# FPGAPower.net
KiCad netlist of a schematic drawn in Altium Designer
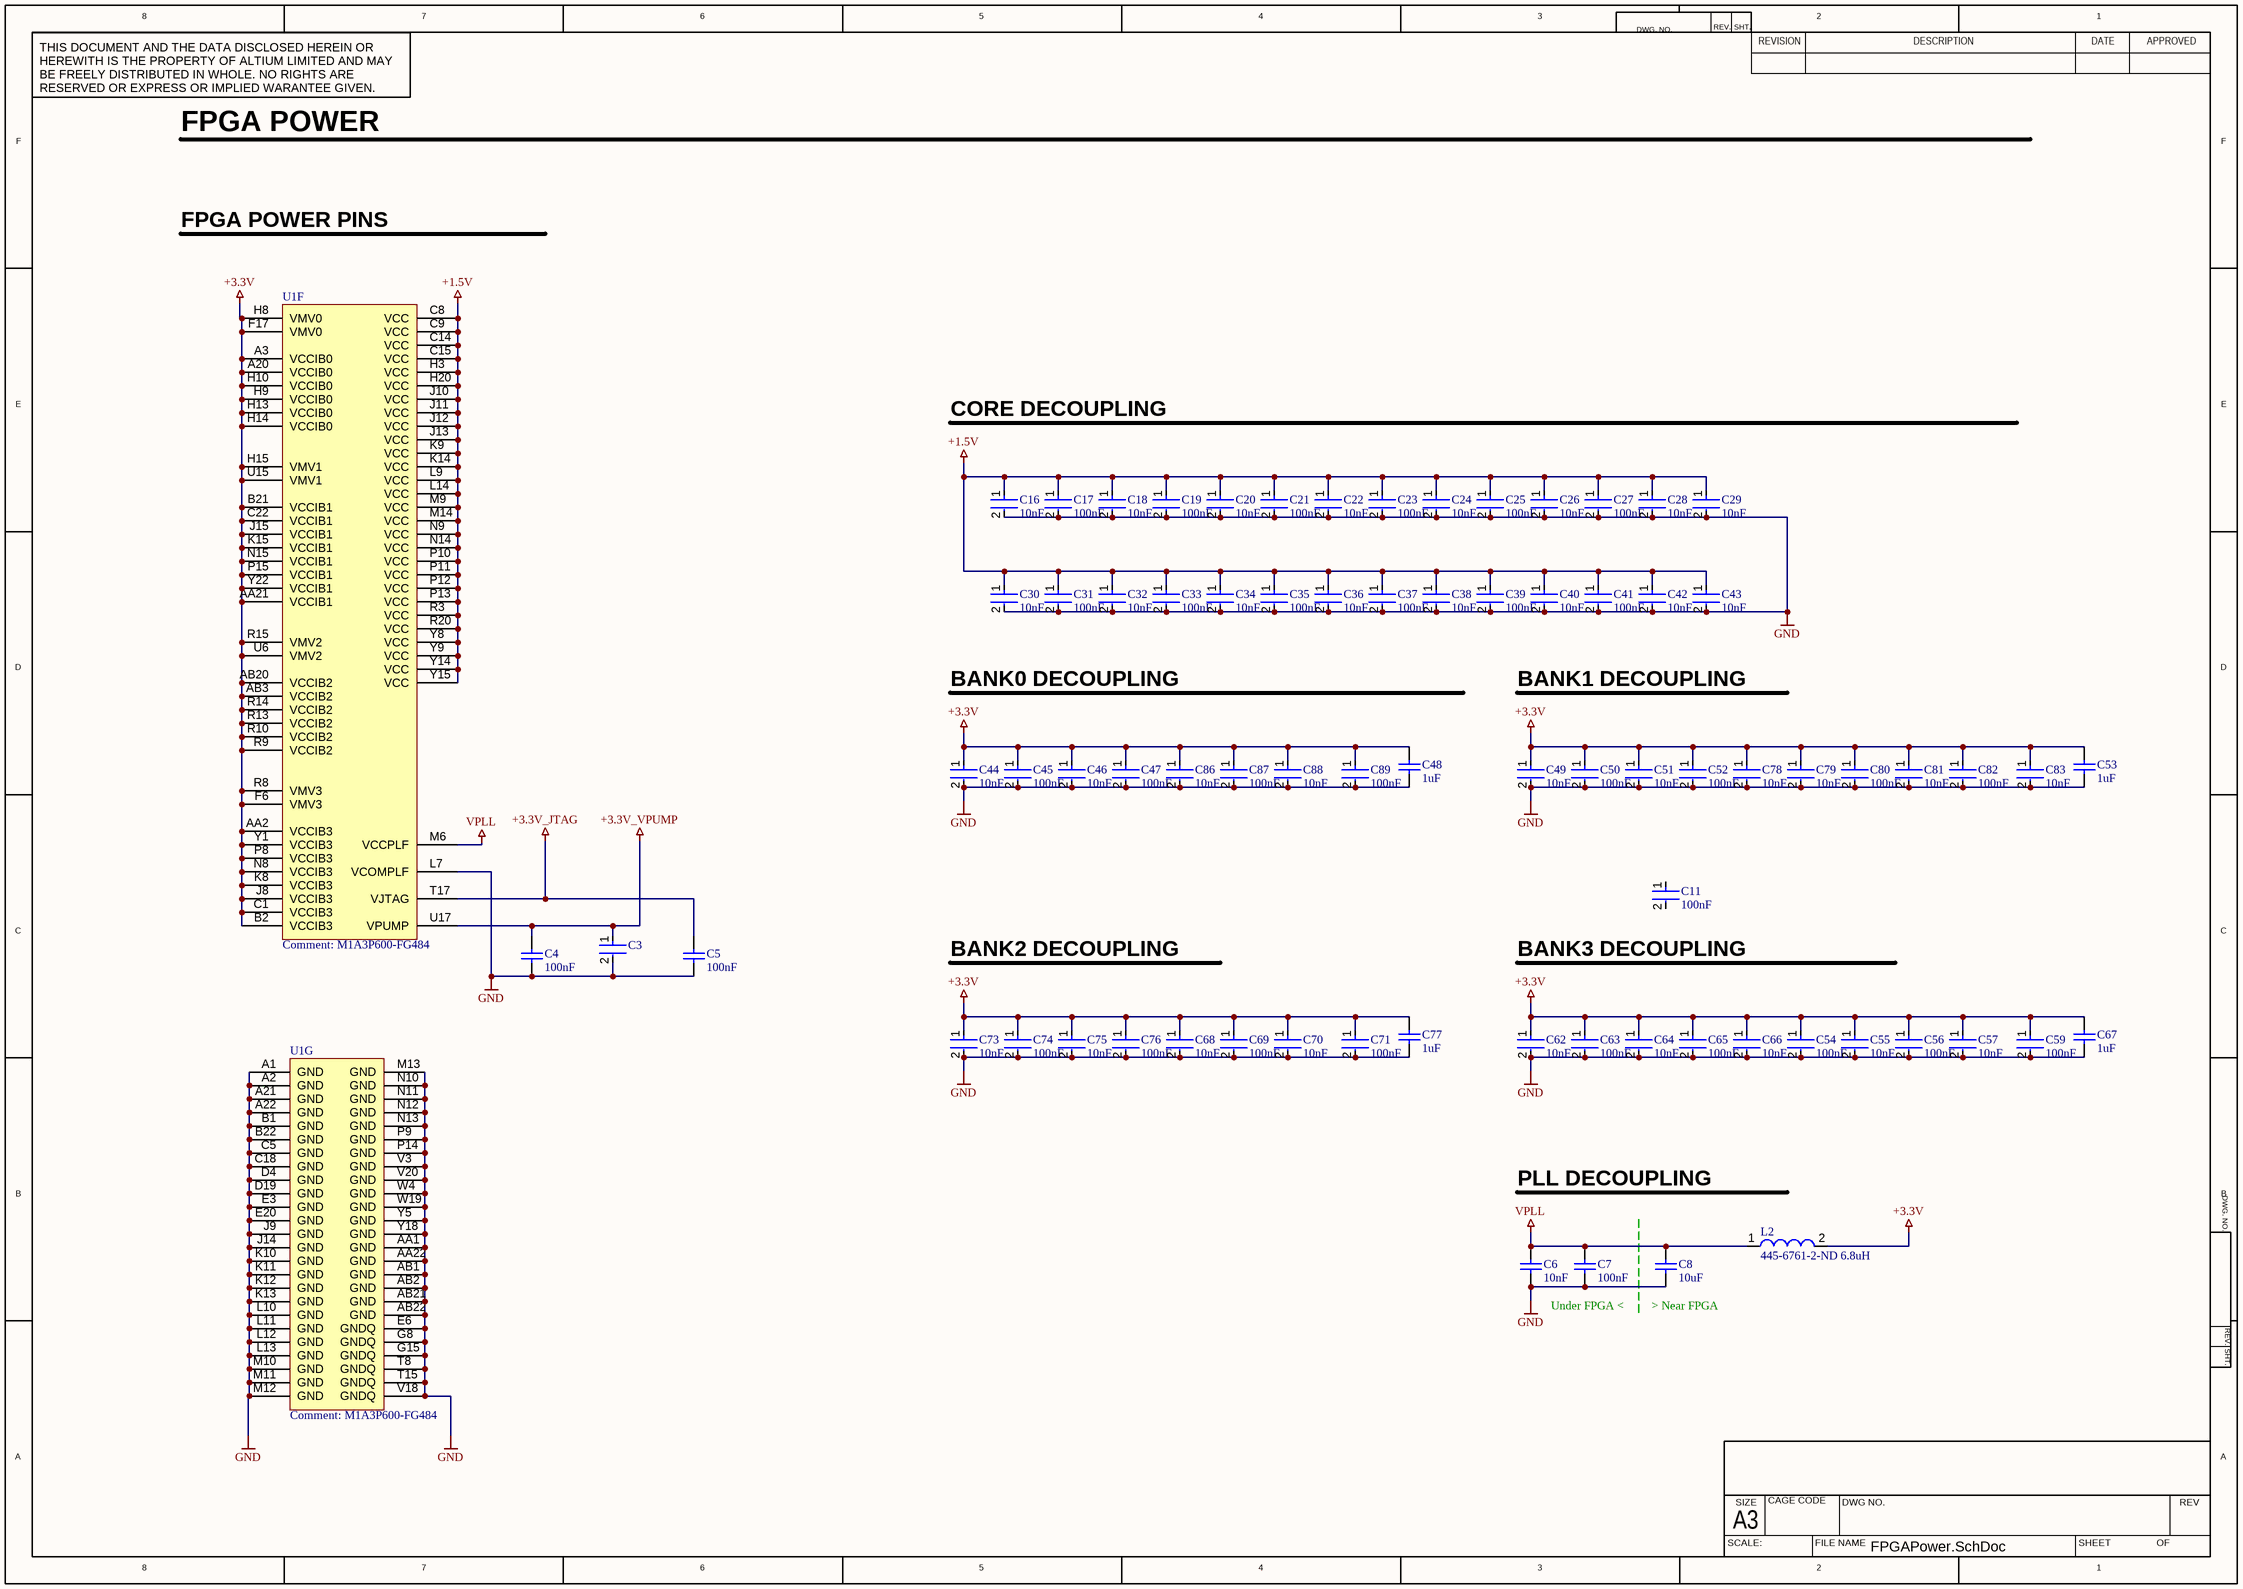
[diagram p0: FPGAPower.SchDoc]

(export (version "E")
  (design (tool "Eeschema 10.0.6"))
  (components
    (comp (ref "C3")
      (value "CC0402KRX5R6BB334")
      (footprint "FP-CC0402-MFG")
      (description "CAP CER 0.33UF 10V X5R 0402")
      (fields
        (field (name "MANUFACTURER") "YAGEO")
        (field (name "OCTOPART") "https://octopart.com/cc0402krx5r6bb334-yageo-21548561")
      )
      (libsource (lib "Altium Content Vault") (part "11868f565c42a9108669ba33697ecf6"))
    )
    (comp (ref "C4")
      (value "100nF")
      (footprint "CAPC1005X60X30ML05T10")
      (fields (field (name "MANUFACTURER") "Kemet") (field (name "PART NUMBER") "C0402C104K8PACTU"))
      (libsource (lib "Altium Content Vault") (part "CAP"))
    )
    (comp (ref "C5")
      (value "100nF")
      (footprint "CAPC1005X60X30ML05T10")
      (fields (field (name "MANUFACTURER") "Kemet") (field (name "PART NUMBER") "C0402C104K8PACTU"))
      (libsource (lib "Altium Content Vault") (part "CAP"))
    )
    (comp (ref "C6")
      (value "10nF")
      (footprint "CAPC0402(1005)60_M")
      (description "CAP 10nF 16V -20% to +80% 0402 (1005 Metric) Thickness 0.6mm SMD")
      (fields (field (name "TOLERANCE") "-20% to +80%"))
      (libsource (lib "Altium Content Vault") (part "CAP"))
    )
    (comp (ref "C7")
      (value "100nF")
      (footprint "CAPC1005X60X30ML05T10")
      (fields (field (name "MANUFACTURER") "Kemet") (field (name "PART NUMBER") "C0402C104K8PACTU"))
      (libsource (lib "Altium Content Vault") (part "CAP"))
    )
    (comp (ref "C8")
      (value "10uF")
      (footprint "CAPC2013X145X20ML20")
      (fields
        (field (name "MANUFACTURER") "TDK")
        (field (name "TOLERANCE") "±10%")
        (field (name "PCN PART NUMBER") "MLCCPartNumberChange30/Nov/2012")
      )
      (libsource (lib "Altium Content Vault") (part "CAP-NP-2"))
    )
    (comp (ref "C11")
      (value "100nF")
      (footprint "FP-GRM155-0_05-IPC_C")
      (fields (field (name "TOLERANCE") "10%") (field (name "VOLTAGE") "25V"))
      (libsource (lib "Altium Content Vault") (part "02cd4be3c70576c341d710602a673aa"))
    )
    (comp (ref "C16")
      (value "10nF")
      (footprint "FP-GRM155-0_05-IPC_C")
      (fields (field (name "TOLERANCE") "10%") (field (name "VOLTAGE") "25V"))
      (libsource (lib "Altium Content Vault") (part "02cd4be3c70576c341d710602a673aa"))
    )
    (comp (ref "C17")
      (value "100nF")
      (footprint "FP-GRM155-0_05-IPC_C")
      (fields (field (name "TOLERANCE") "10%") (field (name "VOLTAGE") "25V"))
      (libsource (lib "Altium Content Vault") (part "02cd4be3c70576c341d710602a673aa"))
    )
    (comp (ref "C18")
      (value "10nF")
      (footprint "FP-GRM155-0_05-IPC_C")
      (fields (field (name "TOLERANCE") "10%") (field (name "VOLTAGE") "25V"))
      (libsource (lib "Altium Content Vault") (part "02cd4be3c70576c341d710602a673aa"))
    )
    (comp (ref "C19")
      (value "100nF")
      (footprint "FP-GRM155-0_05-IPC_C")
      (fields (field (name "TOLERANCE") "10%") (field (name "VOLTAGE") "25V"))
      (libsource (lib "Altium Content Vault") (part "02cd4be3c70576c341d710602a673aa"))
    )
    (comp (ref "C20")
      (value "10nF")
      (footprint "FP-GRM155-0_05-IPC_C")
      (fields (field (name "TOLERANCE") "10%") (field (name "VOLTAGE") "25V"))
      (libsource (lib "Altium Content Vault") (part "02cd4be3c70576c341d710602a673aa"))
    )
    (comp (ref "C21")
      (value "100nF")
      (footprint "FP-GRM155-0_05-IPC_C")
      (fields (field (name "TOLERANCE") "10%") (field (name "VOLTAGE") "25V"))
      (libsource (lib "Altium Content Vault") (part "02cd4be3c70576c341d710602a673aa"))
    )
    (comp (ref "C22")
      (value "10nF")
      (footprint "FP-GRM155-0_05-IPC_C")
      (fields (field (name "TOLERANCE") "10%") (field (name "VOLTAGE") "25V"))
      (libsource (lib "Altium Content Vault") (part "02cd4be3c70576c341d710602a673aa"))
    )
    (comp (ref "C23")
      (value "100nF")
      (footprint "FP-GRM155-0_05-IPC_C")
      (fields (field (name "TOLERANCE") "10%") (field (name "VOLTAGE") "25V"))
      (libsource (lib "Altium Content Vault") (part "02cd4be3c70576c341d710602a673aa"))
    )
    (comp (ref "C24")
      (value "10nF")
      (footprint "FP-GRM155-0_05-IPC_C")
      (fields (field (name "TOLERANCE") "10%") (field (name "VOLTAGE") "25V"))
      (libsource (lib "Altium Content Vault") (part "02cd4be3c70576c341d710602a673aa"))
    )
    (comp (ref "C25")
      (value "100nF")
      (footprint "FP-GRM155-0_05-IPC_C")
      (fields (field (name "TOLERANCE") "10%") (field (name "VOLTAGE") "25V"))
      (libsource (lib "Altium Content Vault") (part "02cd4be3c70576c341d710602a673aa"))
    )
    (comp (ref "C26")
      (value "10nF")
      (footprint "FP-GRM155-0_05-IPC_C")
      (fields (field (name "TOLERANCE") "10%") (field (name "VOLTAGE") "25V"))
      (libsource (lib "Altium Content Vault") (part "02cd4be3c70576c341d710602a673aa"))
    )
    (comp (ref "C27")
      (value "100nF")
      (footprint "FP-GRM155-0_05-IPC_C")
      (fields (field (name "TOLERANCE") "10%") (field (name "VOLTAGE") "25V"))
      (libsource (lib "Altium Content Vault") (part "02cd4be3c70576c341d710602a673aa"))
    )
    (comp (ref "C28")
      (value "10nF")
      (footprint "FP-GRM155-0_05-IPC_C")
      (fields (field (name "TOLERANCE") "10%") (field (name "VOLTAGE") "25V"))
      (libsource (lib "Altium Content Vault") (part "02cd4be3c70576c341d710602a673aa"))
    )
    (comp (ref "C29")
      (value "10nF")
      (footprint "FP-GRM155-0_05-IPC_C")
      (fields (field (name "TOLERANCE") "10%") (field (name "VOLTAGE") "25V"))
      (libsource (lib "Altium Content Vault") (part "02cd4be3c70576c341d710602a673aa"))
    )
    (comp (ref "C30")
      (value "10nF")
      (footprint "FP-GRM155-0_05-IPC_C")
      (fields (field (name "TOLERANCE") "10%") (field (name "VOLTAGE") "25V"))
      (libsource (lib "Altium Content Vault") (part "02cd4be3c70576c341d710602a673aa"))
    )
    (comp (ref "C31")
      (value "100nF")
      (footprint "FP-GRM155-0_05-IPC_C")
      (fields (field (name "TOLERANCE") "10%") (field (name "VOLTAGE") "25V"))
      (libsource (lib "Altium Content Vault") (part "02cd4be3c70576c341d710602a673aa"))
    )
    (comp (ref "C32")
      (value "10nF")
      (footprint "FP-GRM155-0_05-IPC_C")
      (fields (field (name "TOLERANCE") "10%") (field (name "VOLTAGE") "25V"))
      (libsource (lib "Altium Content Vault") (part "02cd4be3c70576c341d710602a673aa"))
    )
    (comp (ref "C33")
      (value "100nF")
      (footprint "FP-GRM155-0_05-IPC_C")
      (fields (field (name "TOLERANCE") "10%") (field (name "VOLTAGE") "25V"))
      (libsource (lib "Altium Content Vault") (part "02cd4be3c70576c341d710602a673aa"))
    )
    (comp (ref "C34")
      (value "10nF")
      (footprint "FP-GRM155-0_05-IPC_C")
      (fields (field (name "TOLERANCE") "10%") (field (name "VOLTAGE") "25V"))
      (libsource (lib "Altium Content Vault") (part "02cd4be3c70576c341d710602a673aa"))
    )
    (comp (ref "C35")
      (value "100nF")
      (footprint "FP-GRM155-0_05-IPC_C")
      (fields (field (name "TOLERANCE") "10%") (field (name "VOLTAGE") "25V"))
      (libsource (lib "Altium Content Vault") (part "02cd4be3c70576c341d710602a673aa"))
    )
    (comp (ref "C36")
      (value "10nF")
      (footprint "FP-GRM155-0_05-IPC_C")
      (fields (field (name "TOLERANCE") "10%") (field (name "VOLTAGE") "25V"))
      (libsource (lib "Altium Content Vault") (part "02cd4be3c70576c341d710602a673aa"))
    )
    (comp (ref "C37")
      (value "100nF")
      (footprint "FP-GRM155-0_05-IPC_C")
      (fields (field (name "TOLERANCE") "10%") (field (name "VOLTAGE") "25V"))
      (libsource (lib "Altium Content Vault") (part "02cd4be3c70576c341d710602a673aa"))
    )
    (comp (ref "C38")
      (value "10nF")
      (footprint "FP-GRM155-0_05-IPC_C")
      (fields (field (name "TOLERANCE") "10%") (field (name "VOLTAGE") "25V"))
      (libsource (lib "Altium Content Vault") (part "02cd4be3c70576c341d710602a673aa"))
    )
    (comp (ref "C39")
      (value "100nF")
      (footprint "FP-GRM155-0_05-IPC_C")
      (fields (field (name "TOLERANCE") "10%") (field (name "VOLTAGE") "25V"))
      (libsource (lib "Altium Content Vault") (part "02cd4be3c70576c341d710602a673aa"))
    )
    (comp (ref "C40")
      (value "10nF")
      (footprint "FP-GRM155-0_05-IPC_C")
      (fields (field (name "TOLERANCE") "10%") (field (name "VOLTAGE") "25V"))
      (libsource (lib "Altium Content Vault") (part "02cd4be3c70576c341d710602a673aa"))
    )
    (comp (ref "C41")
      (value "100nF")
      (footprint "FP-GRM155-0_05-IPC_C")
      (fields (field (name "TOLERANCE") "10%") (field (name "VOLTAGE") "25V"))
      (libsource (lib "Altium Content Vault") (part "02cd4be3c70576c341d710602a673aa"))
    )
    (comp (ref "C42")
      (value "10nF")
      (footprint "FP-GRM155-0_05-IPC_C")
      (fields (field (name "TOLERANCE") "10%") (field (name "VOLTAGE") "25V"))
      (libsource (lib "Altium Content Vault") (part "02cd4be3c70576c341d710602a673aa"))
    )
    (comp (ref "C43")
      (value "10nF")
      (footprint "FP-GRM155-0_05-IPC_C")
      (fields (field (name "TOLERANCE") "10%") (field (name "VOLTAGE") "25V"))
      (libsource (lib "Altium Content Vault") (part "02cd4be3c70576c341d710602a673aa"))
    )
    (comp (ref "C44")
      (value "10nF")
      (footprint "FP-GRM155-0_05-IPC_C")
      (fields (field (name "TOLERANCE") "10%") (field (name "VOLTAGE") "25V"))
      (libsource (lib "Altium Content Vault") (part "02cd4be3c70576c341d710602a673aa"))
    )
    (comp (ref "C45")
      (value "100nF")
      (footprint "FP-GRM155-0_05-IPC_C")
      (fields (field (name "TOLERANCE") "10%") (field (name "VOLTAGE") "25V"))
      (libsource (lib "Altium Content Vault") (part "02cd4be3c70576c341d710602a673aa"))
    )
    (comp (ref "C46")
      (value "10nF")
      (footprint "FP-GRM155-0_05-IPC_C")
      (fields (field (name "TOLERANCE") "10%") (field (name "VOLTAGE") "25V"))
      (libsource (lib "Altium Content Vault") (part "02cd4be3c70576c341d710602a673aa"))
    )
    (comp (ref "C47")
      (value "100nF")
      (footprint "FP-GRM155-0_05-IPC_C")
      (fields (field (name "TOLERANCE") "10%") (field (name "VOLTAGE") "25V"))
      (libsource (lib "Altium Content Vault") (part "02cd4be3c70576c341d710602a673aa"))
    )
    (comp (ref "C48")
      (value "1uF")
      (footprint "CAPC1608X90X20LL10")
      (description "Chip Capacitor, 1 uF, +/- 10%, 50 V, -55 to 85 degC, 0603 (1608 Metric), RoHS, Tape and Reel")
      (fields
        (field (name "MANUFACTURER") "TDK")
        (field (name "PCN PART NUMBER") "MLCCPartNumberChange30/Nov/2012")
      )
      (libsource (lib "Altium Content Vault") (part "CAP-NP-2"))
    )
    (comp (ref "C49")
      (value "10nF")
      (footprint "FP-GRM155-0_05-IPC_C")
      (fields (field (name "TOLERANCE") "10%") (field (name "VOLTAGE") "25V"))
      (libsource (lib "Altium Content Vault") (part "02cd4be3c70576c341d710602a673aa"))
    )
    (comp (ref "C50")
      (value "100nF")
      (footprint "FP-GRM155-0_05-IPC_C")
      (fields (field (name "TOLERANCE") "10%") (field (name "VOLTAGE") "25V"))
      (libsource (lib "Altium Content Vault") (part "02cd4be3c70576c341d710602a673aa"))
    )
    (comp (ref "C51")
      (value "10nF")
      (footprint "FP-GRM155-0_05-IPC_C")
      (fields (field (name "TOLERANCE") "10%") (field (name "VOLTAGE") "25V"))
      (libsource (lib "Altium Content Vault") (part "02cd4be3c70576c341d710602a673aa"))
    )
    (comp (ref "C52")
      (value "100nF")
      (footprint "FP-GRM155-0_05-IPC_C")
      (fields (field (name "TOLERANCE") "10%") (field (name "VOLTAGE") "25V"))
      (libsource (lib "Altium Content Vault") (part "02cd4be3c70576c341d710602a673aa"))
    )
    (comp (ref "C53")
      (value "1uF")
      (footprint "CAPC1608X90X20LL10")
      (description "Chip Capacitor, 1 uF, +/- 10%, 50 V, -55 to 85 degC, 0603 (1608 Metric), RoHS, Tape and Reel")
      (fields
        (field (name "MANUFACTURER") "TDK")
        (field (name "PCN PART NUMBER") "MLCCPartNumberChange30/Nov/2012")
      )
      (libsource (lib "Altium Content Vault") (part "CAP-NP-2"))
    )
    (comp (ref "C54")
      (value "100nF")
      (footprint "FP-GRM155-0_05-IPC_C")
      (fields (field (name "TOLERANCE") "10%") (field (name "VOLTAGE") "25V"))
      (libsource (lib "Altium Content Vault") (part "02cd4be3c70576c341d710602a673aa"))
    )
    (comp (ref "C55")
      (value "10nF")
      (footprint "FP-GRM155-0_05-IPC_C")
      (fields (field (name "TOLERANCE") "10%") (field (name "VOLTAGE") "25V"))
      (libsource (lib "Altium Content Vault") (part "02cd4be3c70576c341d710602a673aa"))
    )
    (comp (ref "C56")
      (value "100nF")
      (footprint "FP-GRM155-0_05-IPC_C")
      (fields (field (name "TOLERANCE") "10%") (field (name "VOLTAGE") "25V"))
      (libsource (lib "Altium Content Vault") (part "02cd4be3c70576c341d710602a673aa"))
    )
    (comp (ref "C57")
      (value "10nF")
      (footprint "FP-GRM155-0_05-IPC_C")
      (fields (field (name "TOLERANCE") "10%") (field (name "VOLTAGE") "25V"))
      (libsource (lib "Altium Content Vault") (part "02cd4be3c70576c341d710602a673aa"))
    )
    (comp (ref "C59")
      (value "100nF")
      (footprint "FP-GRM155-0_05-IPC_C")
      (fields (field (name "TOLERANCE") "10%") (field (name "VOLTAGE") "25V"))
      (libsource (lib "Altium Content Vault") (part "02cd4be3c70576c341d710602a673aa"))
    )
    (comp (ref "C62")
      (value "10nF")
      (footprint "FP-GRM155-0_05-IPC_C")
      (fields (field (name "TOLERANCE") "10%") (field (name "VOLTAGE") "25V"))
      (libsource (lib "Altium Content Vault") (part "02cd4be3c70576c341d710602a673aa"))
    )
    (comp (ref "C63")
      (value "100nF")
      (footprint "FP-GRM155-0_05-IPC_C")
      (fields (field (name "TOLERANCE") "10%") (field (name "VOLTAGE") "25V"))
      (libsource (lib "Altium Content Vault") (part "02cd4be3c70576c341d710602a673aa"))
    )
    (comp (ref "C64")
      (value "10nF")
      (footprint "FP-GRM155-0_05-IPC_C")
      (fields (field (name "TOLERANCE") "10%") (field (name "VOLTAGE") "25V"))
      (libsource (lib "Altium Content Vault") (part "02cd4be3c70576c341d710602a673aa"))
    )
    (comp (ref "C65")
      (value "100nF")
      (footprint "FP-GRM155-0_05-IPC_C")
      (fields (field (name "TOLERANCE") "10%") (field (name "VOLTAGE") "25V"))
      (libsource (lib "Altium Content Vault") (part "02cd4be3c70576c341d710602a673aa"))
    )
    (comp (ref "C66")
      (value "10nF")
      (footprint "FP-GRM155-0_05-IPC_C")
      (fields (field (name "TOLERANCE") "10%") (field (name "VOLTAGE") "25V"))
      (libsource (lib "Altium Content Vault") (part "02cd4be3c70576c341d710602a673aa"))
    )
    (comp (ref "C67")
      (value "1uF")
      (footprint "CAPC1608X90X20LL10")
      (description "Chip Capacitor, 1 uF, +/- 10%, 50 V, -55 to 85 degC, 0603 (1608 Metric), RoHS, Tape and Reel")
      (fields
        (field (name "MANUFACTURER") "TDK")
        (field (name "PCN PART NUMBER") "MLCCPartNumberChange30/Nov/2012")
      )
      (libsource (lib "Altium Content Vault") (part "CAP-NP-2"))
    )
    (comp (ref "C68")
      (value "10nF")
      (footprint "FP-GRM155-0_05-IPC_C")
      (fields (field (name "TOLERANCE") "10%") (field (name "VOLTAGE") "25V"))
      (libsource (lib "Altium Content Vault") (part "02cd4be3c70576c341d710602a673aa"))
    )
    (comp (ref "C69")
      (value "100nF")
      (footprint "FP-GRM155-0_05-IPC_C")
      (fields (field (name "TOLERANCE") "10%") (field (name "VOLTAGE") "25V"))
      (libsource (lib "Altium Content Vault") (part "02cd4be3c70576c341d710602a673aa"))
    )
    (comp (ref "C70")
      (value "10nF")
      (footprint "FP-GRM155-0_05-IPC_C")
      (fields (field (name "TOLERANCE") "10%") (field (name "VOLTAGE") "25V"))
      (libsource (lib "Altium Content Vault") (part "02cd4be3c70576c341d710602a673aa"))
    )
    (comp (ref "C71")
      (value "100nF")
      (footprint "FP-GRM155-0_05-IPC_C")
      (fields (field (name "TOLERANCE") "10%") (field (name "VOLTAGE") "25V"))
      (libsource (lib "Altium Content Vault") (part "02cd4be3c70576c341d710602a673aa"))
    )
    (comp (ref "C73")
      (value "10nF")
      (footprint "FP-GRM155-0_05-IPC_C")
      (fields (field (name "TOLERANCE") "10%") (field (name "VOLTAGE") "25V"))
      (libsource (lib "Altium Content Vault") (part "02cd4be3c70576c341d710602a673aa"))
    )
    (comp (ref "C74")
      (value "100nF")
      (footprint "FP-GRM155-0_05-IPC_C")
      (fields (field (name "TOLERANCE") "10%") (field (name "VOLTAGE") "25V"))
      (libsource (lib "Altium Content Vault") (part "02cd4be3c70576c341d710602a673aa"))
    )
    (comp (ref "C75")
      (value "10nF")
      (footprint "FP-GRM155-0_05-IPC_C")
      (fields (field (name "TOLERANCE") "10%") (field (name "VOLTAGE") "25V"))
      (libsource (lib "Altium Content Vault") (part "02cd4be3c70576c341d710602a673aa"))
    )
    (comp (ref "C76")
      (value "100nF")
      (footprint "FP-GRM155-0_05-IPC_C")
      (fields (field (name "TOLERANCE") "10%") (field (name "VOLTAGE") "25V"))
      (libsource (lib "Altium Content Vault") (part "02cd4be3c70576c341d710602a673aa"))
    )
    (comp (ref "C77")
      (value "1uF")
      (footprint "CAPC1608X90X20LL10")
      (description "Chip Capacitor, 1 uF, +/- 10%, 50 V, -55 to 85 degC, 0603 (1608 Metric), RoHS, Tape and Reel")
      (fields
        (field (name "MANUFACTURER") "TDK")
        (field (name "PCN PART NUMBER") "MLCCPartNumberChange30/Nov/2012")
      )
      (libsource (lib "Altium Content Vault") (part "CAP-NP-2"))
    )
    (comp (ref "C78")
      (value "10nF")
      (footprint "FP-GRM155-0_05-IPC_C")
      (fields (field (name "TOLERANCE") "10%") (field (name "VOLTAGE") "25V"))
      (libsource (lib "Altium Content Vault") (part "02cd4be3c70576c341d710602a673aa"))
    )
    (comp (ref "C79")
      (value "10nF")
      (footprint "FP-GRM155-0_05-IPC_C")
      (fields (field (name "TOLERANCE") "10%") (field (name "VOLTAGE") "25V"))
      (libsource (lib "Altium Content Vault") (part "02cd4be3c70576c341d710602a673aa"))
    )
    (comp (ref "C80")
      (value "100nF")
      (footprint "FP-GRM155-0_05-IPC_C")
      (fields (field (name "TOLERANCE") "10%") (field (name "VOLTAGE") "25V"))
      (libsource (lib "Altium Content Vault") (part "02cd4be3c70576c341d710602a673aa"))
    )
    (comp (ref "C81")
      (value "10nF")
      (footprint "FP-GRM155-0_05-IPC_C")
      (fields (field (name "TOLERANCE") "10%") (field (name "VOLTAGE") "25V"))
      (libsource (lib "Altium Content Vault") (part "02cd4be3c70576c341d710602a673aa"))
    )
    (comp (ref "C82")
      (value "100nF")
      (footprint "FP-GRM155-0_05-IPC_C")
      (fields (field (name "TOLERANCE") "10%") (field (name "VOLTAGE") "25V"))
      (libsource (lib "Altium Content Vault") (part "02cd4be3c70576c341d710602a673aa"))
    )
    (comp (ref "C83")
      (value "10nF")
      (footprint "FP-GRM155-0_05-IPC_C")
      (fields (field (name "TOLERANCE") "10%") (field (name "VOLTAGE") "25V"))
      (libsource (lib "Altium Content Vault") (part "02cd4be3c70576c341d710602a673aa"))
    )
    (comp (ref "C86")
      (value "10nF")
      (footprint "FP-GRM155-0_05-IPC_C")
      (fields (field (name "TOLERANCE") "10%") (field (name "VOLTAGE") "25V"))
      (libsource (lib "Altium Content Vault") (part "02cd4be3c70576c341d710602a673aa"))
    )
    (comp (ref "C87")
      (value "100nF")
      (footprint "FP-GRM155-0_05-IPC_C")
      (fields (field (name "TOLERANCE") "10%") (field (name "VOLTAGE") "25V"))
      (libsource (lib "Altium Content Vault") (part "02cd4be3c70576c341d710602a673aa"))
    )
    (comp (ref "C88")
      (value "10nF")
      (footprint "FP-GRM155-0_05-IPC_C")
      (fields (field (name "TOLERANCE") "10%") (field (name "VOLTAGE") "25V"))
      (libsource (lib "Altium Content Vault") (part "02cd4be3c70576c341d710602a673aa"))
    )
    (comp (ref "C89")
      (value "100nF")
      (footprint "FP-GRM155-0_05-IPC_C")
      (fields (field (name "TOLERANCE") "10%") (field (name "VOLTAGE") "25V"))
      (libsource (lib "Altium Content Vault") (part "02cd4be3c70576c341d710602a673aa"))
    )
    (comp (ref "L2")
      (value "445-6761-2-ND 6.8uH")
      (footprint "SMD-0805")
      (description "SMD-Multilayer Inductor WE-MI, L = 1.00 µH")
      (libsource (lib "Altium Content Vault") (part "PAS-IND-INDUCTOR-2"))
    )
    (comp (ref "U1")
      (value "M1A3P600-FG484")
      (footprint "FG484")
      (libsource (lib "Altium Content Vault") (part "FPGA-ACTPA3-A3P600-GA484"))
    )
  )
  (nets
    (net (code "1") (name "+1.5V") (class "Default")
      (node (ref "C16") (pin "1") (pinfunction "1_1") (pintype "passive"))
      (node (ref "C17") (pin "1") (pinfunction "1_1") (pintype "passive"))
      (node (ref "C18") (pin "1") (pinfunction "1_1") (pintype "passive"))
      (node (ref "C19") (pin "1") (pinfunction "1_1") (pintype "passive"))
      (node (ref "C20") (pin "1") (pinfunction "1_1") (pintype "passive"))
      (node (ref "C21") (pin "1") (pinfunction "1_1") (pintype "passive"))
      (node (ref "C22") (pin "1") (pinfunction "1_1") (pintype "passive"))
      (node (ref "C23") (pin "1") (pinfunction "1_1") (pintype "passive"))
      (node (ref "C24") (pin "1") (pinfunction "1_1") (pintype "passive"))
      (node (ref "C25") (pin "1") (pinfunction "1_1") (pintype "passive"))
      (node (ref "C26") (pin "1") (pinfunction "1_1") (pintype "passive"))
      (node (ref "C27") (pin "1") (pinfunction "1_1") (pintype "passive"))
      (node (ref "C28") (pin "1") (pinfunction "1_1") (pintype "passive"))
      (node (ref "C29") (pin "1") (pinfunction "1_1") (pintype "passive"))
      (node (ref "C30") (pin "1") (pinfunction "1_1") (pintype "passive"))
      (node (ref "C31") (pin "1") (pinfunction "1_1") (pintype "passive"))
      (node (ref "C32") (pin "1") (pinfunction "1_1") (pintype "passive"))
      (node (ref "C33") (pin "1") (pinfunction "1_1") (pintype "passive"))
      (node (ref "C34") (pin "1") (pinfunction "1_1") (pintype "passive"))
      (node (ref "C35") (pin "1") (pinfunction "1_1") (pintype "passive"))
      (node (ref "C36") (pin "1") (pinfunction "1_1") (pintype "passive"))
      (node (ref "C37") (pin "1") (pinfunction "1_1") (pintype "passive"))
      (node (ref "C38") (pin "1") (pinfunction "1_1") (pintype "passive"))
      (node (ref "C39") (pin "1") (pinfunction "1_1") (pintype "passive"))
      (node (ref "C40") (pin "1") (pinfunction "1_1") (pintype "passive"))
      (node (ref "C41") (pin "1") (pinfunction "1_1") (pintype "passive"))
      (node (ref "C42") (pin "1") (pinfunction "1_1") (pintype "passive"))
      (node (ref "C43") (pin "1") (pinfunction "1_1") (pintype "passive"))
      (node (ref "U1") (pin "C14") (pinfunction "VCC_C14") (pintype "power_in"))
      (node (ref "U1") (pin "C15") (pinfunction "VCC_C15") (pintype "power_in"))
      (node (ref "U1") (pin "C8") (pinfunction "VCC_C8") (pintype "power_in"))
      (node (ref "U1") (pin "C9") (pinfunction "VCC_C9") (pintype "power_in"))
      (node (ref "U1") (pin "H20") (pinfunction "VCC_H20") (pintype "power_in"))
      (node (ref "U1") (pin "H3") (pinfunction "VCC_H3") (pintype "power_in"))
      (node (ref "U1") (pin "J10") (pinfunction "VCC_J10") (pintype "power_in"))
      (node (ref "U1") (pin "J11") (pinfunction "VCC_J11") (pintype "power_in"))
      (node (ref "U1") (pin "J12") (pinfunction "VCC_J12") (pintype "power_in"))
      (node (ref "U1") (pin "J13") (pinfunction "VCC_J13") (pintype "power_in"))
      (node (ref "U1") (pin "K14") (pinfunction "VCC_K14") (pintype "power_in"))
      (node (ref "U1") (pin "K9") (pinfunction "VCC_K9") (pintype "power_in"))
      (node (ref "U1") (pin "L14") (pinfunction "VCC_L14") (pintype "power_in"))
      (node (ref "U1") (pin "L9") (pinfunction "VCC_L9") (pintype "power_in"))
      (node (ref "U1") (pin "M14") (pinfunction "VCC_M14") (pintype "power_in"))
      (node (ref "U1") (pin "M9") (pinfunction "VCC_M9") (pintype "power_in"))
      (node (ref "U1") (pin "N14") (pinfunction "VCC_N14") (pintype "power_in"))
      (node (ref "U1") (pin "N9") (pinfunction "VCC_N9") (pintype "power_in"))
      (node (ref "U1") (pin "P10") (pinfunction "VCC_P10") (pintype "power_in"))
      (node (ref "U1") (pin "P11") (pinfunction "VCC_P11") (pintype "power_in"))
      (node (ref "U1") (pin "P12") (pinfunction "VCC_P12") (pintype "power_in"))
      (node (ref "U1") (pin "P13") (pinfunction "VCC_P13") (pintype "power_in"))
      (node (ref "U1") (pin "R20") (pinfunction "VCC_R20") (pintype "power_in"))
      (node (ref "U1") (pin "R3") (pinfunction "VCC_R3") (pintype "power_in"))
      (node (ref "U1") (pin "Y14") (pinfunction "VCC_Y14") (pintype "power_in"))
      (node (ref "U1") (pin "Y15") (pinfunction "VCC_Y15") (pintype "power_in"))
      (node (ref "U1") (pin "Y8") (pinfunction "VCC_Y8") (pintype "power_in"))
      (node (ref "U1") (pin "Y9") (pinfunction "VCC_Y9") (pintype "power_in"))
    )
    (net (code "2") (name "+3.3V") (class "Default")
      (node (ref "C44") (pin "1") (pinfunction "1_1") (pintype "passive"))
      (node (ref "C45") (pin "1") (pinfunction "1_1") (pintype "passive"))
      (node (ref "C46") (pin "1") (pinfunction "1_1") (pintype "passive"))
      (node (ref "C47") (pin "1") (pinfunction "1_1") (pintype "passive"))
      (node (ref "C48") (pin "2") (pinfunction "2_2") (pintype "passive"))
      (node (ref "C49") (pin "1") (pinfunction "1_1") (pintype "passive"))
      (node (ref "C50") (pin "1") (pinfunction "1_1") (pintype "passive"))
      (node (ref "C51") (pin "1") (pinfunction "1_1") (pintype "passive"))
      (node (ref "C52") (pin "1") (pinfunction "1_1") (pintype "passive"))
      (node (ref "C53") (pin "2") (pinfunction "2_2") (pintype "passive"))
      (node (ref "C54") (pin "1") (pinfunction "1_1") (pintype "passive"))
      (node (ref "C55") (pin "1") (pinfunction "1_1") (pintype "passive"))
      (node (ref "C56") (pin "1") (pinfunction "1_1") (pintype "passive"))
      (node (ref "C57") (pin "1") (pinfunction "1_1") (pintype "passive"))
      (node (ref "C59") (pin "1") (pinfunction "1_1") (pintype "passive"))
      (node (ref "C62") (pin "1") (pinfunction "1_1") (pintype "passive"))
      (node (ref "C63") (pin "1") (pinfunction "1_1") (pintype "passive"))
      (node (ref "C64") (pin "1") (pinfunction "1_1") (pintype "passive"))
      (node (ref "C65") (pin "1") (pinfunction "1_1") (pintype "passive"))
      (node (ref "C66") (pin "1") (pinfunction "1_1") (pintype "passive"))
      (node (ref "C67") (pin "2") (pinfunction "2_2") (pintype "passive"))
      (node (ref "C68") (pin "1") (pinfunction "1_1") (pintype "passive"))
      (node (ref "C69") (pin "1") (pinfunction "1_1") (pintype "passive"))
      (node (ref "C70") (pin "1") (pinfunction "1_1") (pintype "passive"))
      (node (ref "C71") (pin "1") (pinfunction "1_1") (pintype "passive"))
      (node (ref "C73") (pin "1") (pinfunction "1_1") (pintype "passive"))
      (node (ref "C74") (pin "1") (pinfunction "1_1") (pintype "passive"))
      (node (ref "C75") (pin "1") (pinfunction "1_1") (pintype "passive"))
      (node (ref "C76") (pin "1") (pinfunction "1_1") (pintype "passive"))
      (node (ref "C77") (pin "2") (pinfunction "2_2") (pintype "passive"))
      (node (ref "C78") (pin "1") (pinfunction "1_1") (pintype "passive"))
      (node (ref "C79") (pin "1") (pinfunction "1_1") (pintype "passive"))
      (node (ref "C80") (pin "1") (pinfunction "1_1") (pintype "passive"))
      (node (ref "C81") (pin "1") (pinfunction "1_1") (pintype "passive"))
      (node (ref "C82") (pin "1") (pinfunction "1_1") (pintype "passive"))
      (node (ref "C83") (pin "1") (pinfunction "1_1") (pintype "passive"))
      (node (ref "C86") (pin "1") (pinfunction "1_1") (pintype "passive"))
      (node (ref "C87") (pin "1") (pinfunction "1_1") (pintype "passive"))
      (node (ref "C88") (pin "1") (pinfunction "1_1") (pintype "passive"))
      (node (ref "C89") (pin "1") (pinfunction "1_1") (pintype "passive"))
      (node (ref "L2") (pin "2") (pinfunction "2_2") (pintype "passive"))
      (node (ref "U1") (pin "A20") (pinfunction "VCCIB0_A20") (pintype "power_in"))
      (node (ref "U1") (pin "A3") (pinfunction "VCCIB0_A3") (pintype "power_in"))
      (node (ref "U1") (pin "AA2") (pinfunction "VCCIB3_AA2") (pintype "power_in"))
      (node (ref "U1") (pin "AA21") (pinfunction "VCCIB1_AA21") (pintype "power_in"))
      (node (ref "U1") (pin "AB20") (pinfunction "VCCIB2_AB20") (pintype "power_in"))
      (node (ref "U1") (pin "AB3") (pinfunction "VCCIB2_AB3") (pintype "power_in"))
      (node (ref "U1") (pin "B2") (pinfunction "VCCIB3_B2") (pintype "power_in"))
      (node (ref "U1") (pin "B21") (pinfunction "VCCIB1_B21") (pintype "power_in"))
      (node (ref "U1") (pin "C1") (pinfunction "VCCIB3_C1") (pintype "power_in"))
      (node (ref "U1") (pin "C22") (pinfunction "VCCIB1_C22") (pintype "power_in"))
      (node (ref "U1") (pin "F17") (pinfunction "VMV0_F17") (pintype "power_in"))
      (node (ref "U1") (pin "F6") (pinfunction "VMV3_F6") (pintype "power_in"))
      (node (ref "U1") (pin "H10") (pinfunction "VCCIB0_H10") (pintype "power_in"))
      (node (ref "U1") (pin "H13") (pinfunction "VCCIB0_H13") (pintype "power_in"))
      (node (ref "U1") (pin "H14") (pinfunction "VCCIB0_H14") (pintype "power_in"))
      (node (ref "U1") (pin "H15") (pinfunction "VMV1_H15") (pintype "power_in"))
      (node (ref "U1") (pin "H8") (pinfunction "VMV0_H8") (pintype "power_in"))
      (node (ref "U1") (pin "H9") (pinfunction "VCCIB0_H9") (pintype "power_in"))
      (node (ref "U1") (pin "J15") (pinfunction "VCCIB1_J15") (pintype "power_in"))
      (node (ref "U1") (pin "J8") (pinfunction "VCCIB3_J8") (pintype "power_in"))
      (node (ref "U1") (pin "K15") (pinfunction "VCCIB1_K15") (pintype "power_in"))
      (node (ref "U1") (pin "K8") (pinfunction "VCCIB3_K8") (pintype "power_in"))
      (node (ref "U1") (pin "N15") (pinfunction "VCCIB1_N15") (pintype "power_in"))
      (node (ref "U1") (pin "N8") (pinfunction "VCCIB3_N8") (pintype "power_in"))
      (node (ref "U1") (pin "P15") (pinfunction "VCCIB1_P15") (pintype "power_in"))
      (node (ref "U1") (pin "P8") (pinfunction "VCCIB3_P8") (pintype "power_in"))
      (node (ref "U1") (pin "R10") (pinfunction "VCCIB2_R10") (pintype "power_in"))
      (node (ref "U1") (pin "R13") (pinfunction "VCCIB2_R13") (pintype "power_in"))
      (node (ref "U1") (pin "R14") (pinfunction "VCCIB2_R14") (pintype "power_in"))
      (node (ref "U1") (pin "R15") (pinfunction "VMV2_R15") (pintype "power_in"))
      (node (ref "U1") (pin "R8") (pinfunction "VMV3_R8") (pintype "power_in"))
      (node (ref "U1") (pin "R9") (pinfunction "VCCIB2_R9") (pintype "power_in"))
      (node (ref "U1") (pin "U15") (pinfunction "VMV1_U15") (pintype "power_in"))
      (node (ref "U1") (pin "U6") (pinfunction "VMV2_U6") (pintype "power_in"))
      (node (ref "U1") (pin "Y1") (pinfunction "VCCIB3_Y1") (pintype "power_in"))
      (node (ref "U1") (pin "Y22") (pinfunction "VCCIB1_Y22") (pintype "power_in"))
    )
    (net (code "3") (name "+3.3V_JTAG") (class "Default")
      (node (ref "C5") (pin "2") (pinfunction "2_2") (pintype "passive"))
      (node (ref "U1") (pin "T17") (pinfunction "VJTAG_T17") (pintype "power_in"))
    )
    (net (code "4") (name "+3.3V_VPUMP") (class "Default")
      (node (ref "C3") (pin "1") (pinfunction "1_1") (pintype "passive"))
      (node (ref "C4") (pin "2") (pinfunction "2_2") (pintype "passive"))
      (node (ref "U1") (pin "U17") (pinfunction "VPUMP_U17") (pintype "power_in"))
    )
    (net (code "5") (name "GND") (class "Default")
      (node (ref "C16") (pin "2") (pinfunction "2_2") (pintype "passive"))
      (node (ref "C17") (pin "2") (pinfunction "2_2") (pintype "passive"))
      (node (ref "C18") (pin "2") (pinfunction "2_2") (pintype "passive"))
      (node (ref "C19") (pin "2") (pinfunction "2_2") (pintype "passive"))
      (node (ref "C20") (pin "2") (pinfunction "2_2") (pintype "passive"))
      (node (ref "C21") (pin "2") (pinfunction "2_2") (pintype "passive"))
      (node (ref "C22") (pin "2") (pinfunction "2_2") (pintype "passive"))
      (node (ref "C23") (pin "2") (pinfunction "2_2") (pintype "passive"))
      (node (ref "C24") (pin "2") (pinfunction "2_2") (pintype "passive"))
      (node (ref "C25") (pin "2") (pinfunction "2_2") (pintype "passive"))
      (node (ref "C26") (pin "2") (pinfunction "2_2") (pintype "passive"))
      (node (ref "C27") (pin "2") (pinfunction "2_2") (pintype "passive"))
      (node (ref "C28") (pin "2") (pinfunction "2_2") (pintype "passive"))
      (node (ref "C29") (pin "2") (pinfunction "2_2") (pintype "passive"))
      (node (ref "C3") (pin "2") (pinfunction "2_2") (pintype "passive"))
      (node (ref "C30") (pin "2") (pinfunction "2_2") (pintype "passive"))
      (node (ref "C31") (pin "2") (pinfunction "2_2") (pintype "passive"))
      (node (ref "C32") (pin "2") (pinfunction "2_2") (pintype "passive"))
      (node (ref "C33") (pin "2") (pinfunction "2_2") (pintype "passive"))
      (node (ref "C34") (pin "2") (pinfunction "2_2") (pintype "passive"))
      (node (ref "C35") (pin "2") (pinfunction "2_2") (pintype "passive"))
      (node (ref "C36") (pin "2") (pinfunction "2_2") (pintype "passive"))
      (node (ref "C37") (pin "2") (pinfunction "2_2") (pintype "passive"))
      (node (ref "C38") (pin "2") (pinfunction "2_2") (pintype "passive"))
      (node (ref "C39") (pin "2") (pinfunction "2_2") (pintype "passive"))
      (node (ref "C4") (pin "1") (pinfunction "1_1") (pintype "passive"))
      (node (ref "C40") (pin "2") (pinfunction "2_2") (pintype "passive"))
      (node (ref "C41") (pin "2") (pinfunction "2_2") (pintype "passive"))
      (node (ref "C42") (pin "2") (pinfunction "2_2") (pintype "passive"))
      (node (ref "C43") (pin "2") (pinfunction "2_2") (pintype "passive"))
      (node (ref "C44") (pin "2") (pinfunction "2_2") (pintype "passive"))
      (node (ref "C45") (pin "2") (pinfunction "2_2") (pintype "passive"))
      (node (ref "C46") (pin "2") (pinfunction "2_2") (pintype "passive"))
      (node (ref "C47") (pin "2") (pinfunction "2_2") (pintype "passive"))
      (node (ref "C48") (pin "1") (pinfunction "1_1") (pintype "passive"))
      (node (ref "C49") (pin "2") (pinfunction "2_2") (pintype "passive"))
      (node (ref "C5") (pin "1") (pinfunction "1_1") (pintype "passive"))
      (node (ref "C50") (pin "2") (pinfunction "2_2") (pintype "passive"))
      (node (ref "C51") (pin "2") (pinfunction "2_2") (pintype "passive"))
      (node (ref "C52") (pin "2") (pinfunction "2_2") (pintype "passive"))
      (node (ref "C53") (pin "1") (pinfunction "1_1") (pintype "passive"))
      (node (ref "C54") (pin "2") (pinfunction "2_2") (pintype "passive"))
      (node (ref "C55") (pin "2") (pinfunction "2_2") (pintype "passive"))
      (node (ref "C56") (pin "2") (pinfunction "2_2") (pintype "passive"))
      (node (ref "C57") (pin "2") (pinfunction "2_2") (pintype "passive"))
      (node (ref "C59") (pin "2") (pinfunction "2_2") (pintype "passive"))
      (node (ref "C6") (pin "1") (pinfunction "1_1") (pintype "passive"))
      (node (ref "C62") (pin "2") (pinfunction "2_2") (pintype "passive"))
      (node (ref "C63") (pin "2") (pinfunction "2_2") (pintype "passive"))
      (node (ref "C64") (pin "2") (pinfunction "2_2") (pintype "passive"))
      (node (ref "C65") (pin "2") (pinfunction "2_2") (pintype "passive"))
      (node (ref "C66") (pin "2") (pinfunction "2_2") (pintype "passive"))
      (node (ref "C67") (pin "1") (pinfunction "1_1") (pintype "passive"))
      (node (ref "C68") (pin "2") (pinfunction "2_2") (pintype "passive"))
      (node (ref "C69") (pin "2") (pinfunction "2_2") (pintype "passive"))
      (node (ref "C7") (pin "1") (pinfunction "1_1") (pintype "passive"))
      (node (ref "C70") (pin "2") (pinfunction "2_2") (pintype "passive"))
      (node (ref "C71") (pin "2") (pinfunction "2_2") (pintype "passive"))
      (node (ref "C73") (pin "2") (pinfunction "2_2") (pintype "passive"))
      (node (ref "C74") (pin "2") (pinfunction "2_2") (pintype "passive"))
      (node (ref "C75") (pin "2") (pinfunction "2_2") (pintype "passive"))
      (node (ref "C76") (pin "2") (pinfunction "2_2") (pintype "passive"))
      (node (ref "C77") (pin "1") (pinfunction "1_1") (pintype "passive"))
      (node (ref "C78") (pin "2") (pinfunction "2_2") (pintype "passive"))
      (node (ref "C79") (pin "2") (pinfunction "2_2") (pintype "passive"))
      (node (ref "C8") (pin "1") (pinfunction "1_1") (pintype "passive"))
      (node (ref "C80") (pin "2") (pinfunction "2_2") (pintype "passive"))
      (node (ref "C81") (pin "2") (pinfunction "2_2") (pintype "passive"))
      (node (ref "C82") (pin "2") (pinfunction "2_2") (pintype "passive"))
      (node (ref "C83") (pin "2") (pinfunction "2_2") (pintype "passive"))
      (node (ref "C86") (pin "2") (pinfunction "2_2") (pintype "passive"))
      (node (ref "C87") (pin "2") (pinfunction "2_2") (pintype "passive"))
      (node (ref "C88") (pin "2") (pinfunction "2_2") (pintype "passive"))
      (node (ref "C89") (pin "2") (pinfunction "2_2") (pintype "passive"))
      (node (ref "U1") (pin "A1") (pinfunction "GND_A1") (pintype "power_in"))
      (node (ref "U1") (pin "A2") (pinfunction "GND_A2") (pintype "power_in"))
      (node (ref "U1") (pin "A21") (pinfunction "GND_A21") (pintype "power_in"))
      (node (ref "U1") (pin "A22") (pinfunction "GND_A22") (pintype "power_in"))
      (node (ref "U1") (pin "AA1") (pinfunction "GND_AA1") (pintype "power_in"))
      (node (ref "U1") (pin "AA22") (pinfunction "GND_AA22") (pintype "power_in"))
      (node (ref "U1") (pin "AB1") (pinfunction "GND_AB1") (pintype "power_in"))
      (node (ref "U1") (pin "AB2") (pinfunction "GND_AB2") (pintype "power_in"))
      (node (ref "U1") (pin "AB21") (pinfunction "GND_AB21") (pintype "power_in"))
      (node (ref "U1") (pin "AB22") (pinfunction "GND_AB22") (pintype "power_in"))
      (node (ref "U1") (pin "B1") (pinfunction "GND_B1") (pintype "power_in"))
      (node (ref "U1") (pin "B22") (pinfunction "GND_B22") (pintype "power_in"))
      (node (ref "U1") (pin "C18") (pinfunction "GND_C18") (pintype "power_in"))
      (node (ref "U1") (pin "C5") (pinfunction "GND_C5") (pintype "power_in"))
      (node (ref "U1") (pin "D19") (pinfunction "GND_D19") (pintype "power_in"))
      (node (ref "U1") (pin "D4") (pinfunction "GND_D4") (pintype "power_in"))
      (node (ref "U1") (pin "E20") (pinfunction "GND_E20") (pintype "power_in"))
      (node (ref "U1") (pin "E3") (pinfunction "GND_E3") (pintype "power_in"))
      (node (ref "U1") (pin "E6") (pinfunction "GNDQ_E6") (pintype "power_in"))
      (node (ref "U1") (pin "G15") (pinfunction "GNDQ_G15") (pintype "power_in"))
      (node (ref "U1") (pin "G8") (pinfunction "GNDQ_G8") (pintype "power_in"))
      (node (ref "U1") (pin "J14") (pinfunction "GND_J14") (pintype "power_in"))
      (node (ref "U1") (pin "J9") (pinfunction "GND_J9") (pintype "power_in"))
      (node (ref "U1") (pin "K10") (pinfunction "GND_K10") (pintype "power_in"))
      (node (ref "U1") (pin "K11") (pinfunction "GND_K11") (pintype "power_in"))
      (node (ref "U1") (pin "K12") (pinfunction "GND_K12") (pintype "power_in"))
      (node (ref "U1") (pin "K13") (pinfunction "GND_K13") (pintype "power_in"))
      (node (ref "U1") (pin "L10") (pinfunction "GND_L10") (pintype "power_in"))
      (node (ref "U1") (pin "L11") (pinfunction "GND_L11") (pintype "power_in"))
      (node (ref "U1") (pin "L12") (pinfunction "GND_L12") (pintype "power_in"))
      (node (ref "U1") (pin "L13") (pinfunction "GND_L13") (pintype "power_in"))
      (node (ref "U1") (pin "L7") (pinfunction "VCOMPLF_L7") (pintype "power_in"))
      (node (ref "U1") (pin "M10") (pinfunction "GND_M10") (pintype "power_in"))
      (node (ref "U1") (pin "M11") (pinfunction "GND_M11") (pintype "power_in"))
      (node (ref "U1") (pin "M12") (pinfunction "GND_M12") (pintype "power_in"))
      (node (ref "U1") (pin "M13") (pinfunction "GND_M13") (pintype "power_in"))
      (node (ref "U1") (pin "N10") (pinfunction "GND_N10") (pintype "power_in"))
      (node (ref "U1") (pin "N11") (pinfunction "GND_N11") (pintype "power_in"))
      (node (ref "U1") (pin "N12") (pinfunction "GND_N12") (pintype "power_in"))
      (node (ref "U1") (pin "N13") (pinfunction "GND_N13") (pintype "power_in"))
      (node (ref "U1") (pin "P14") (pinfunction "GND_P14") (pintype "power_in"))
      (node (ref "U1") (pin "P9") (pinfunction "GND_P9") (pintype "power_in"))
      (node (ref "U1") (pin "T15") (pinfunction "GNDQ_T15") (pintype "power_in"))
      (node (ref "U1") (pin "T8") (pinfunction "GNDQ_T8") (pintype "power_in"))
      (node (ref "U1") (pin "V18") (pinfunction "GNDQ_V18") (pintype "power_in"))
      (node (ref "U1") (pin "V20") (pinfunction "GND_V20") (pintype "power_in"))
      (node (ref "U1") (pin "V3") (pinfunction "GND_V3") (pintype "power_in"))
      (node (ref "U1") (pin "W19") (pinfunction "GND_W19") (pintype "power_in"))
      (node (ref "U1") (pin "W4") (pinfunction "GND_W4") (pintype "power_in"))
      (node (ref "U1") (pin "Y18") (pinfunction "GND_Y18") (pintype "power_in"))
      (node (ref "U1") (pin "Y5") (pinfunction "GND_Y5") (pintype "power_in"))
    )
    (net (code "6") (name "VPLL") (class "Default")
      (node (ref "C6") (pin "2") (pinfunction "2_2") (pintype "passive"))
      (node (ref "C7") (pin "2") (pinfunction "2_2") (pintype "passive"))
      (node (ref "C8") (pin "2") (pinfunction "2_2") (pintype "passive"))
      (node (ref "L2") (pin "1") (pinfunction "1_1") (pintype "passive"))
      (node (ref "U1") (pin "M6") (pinfunction "VCCPLF_M6") (pintype "power_in"))
    )
    (net (code "7") (name "unconnected-(C11-Pad1)") (class "Default")
      (node (ref "C11") (pin "1") (pinfunction "1_1") (pintype "passive"))
    )
    (net (code "8") (name "unconnected-(C11-Pad2)") (class "Default")
      (node (ref "C11") (pin "2") (pinfunction "2_2") (pintype "passive"))
    )
  )
)
